# vONE-UNO.net
KiCad netlist of a schematic drawn in EAGLE
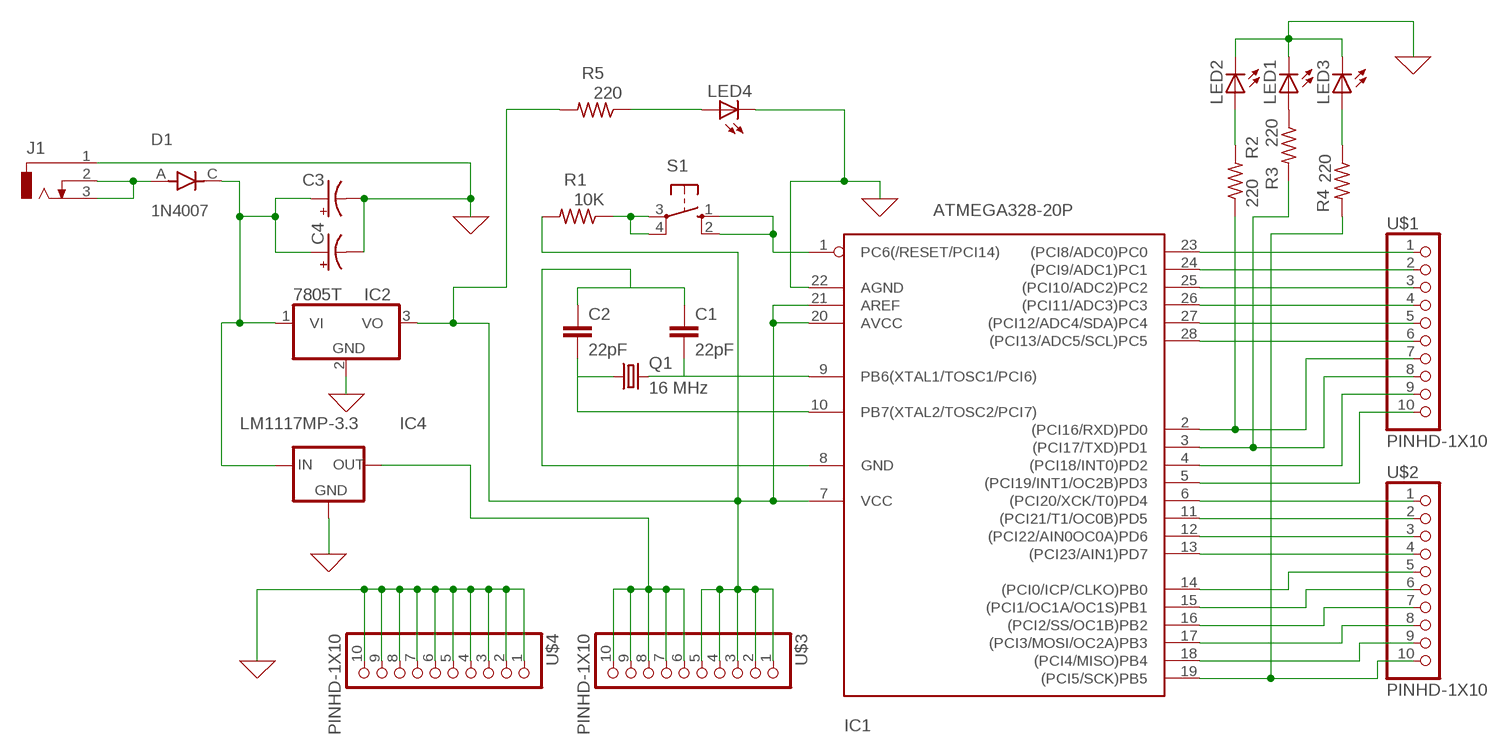
[diagram p0: schematic, sheet 1]

(export (version "E")
  (design (tool "Eeschema 10.0.6"))
  (components
    (comp (ref "C1")
      (value "22pF")
      (footprint "eagle-import:C2.5-3")
      (libsource (lib "eagle-import") (part "C2,5-3"))
    )
    (comp (ref "C2")
      (value "22pF")
      (footprint "eagle-import:C2.5-3")
      (libsource (lib "eagle-import") (part "C2,5-3"))
    )
    (comp (ref "C3")
      (value "CPOL-USE2,5-6E")
      (footprint "eagle-import:E2,5-6E")
      (libsource (lib "eagle-import") (part "CPOL-USE2,5-6E"))
    )
    (comp (ref "C4")
      (value "CPOL-USE2,5-6E")
      (footprint "eagle-import:E2,5-6E")
      (libsource (lib "eagle-import") (part "CPOL-USE2,5-6E"))
    )
    (comp (ref "D1")
      (value "1N4007")
      (footprint "eagle-import:DIOAD1060W80L520D270")
      (fields (field (name "MF") "ON Semiconductor"))
      (libsource (lib "eagle-import") (part "1N4007"))
    )
    (comp (ref "IC1")
      (value "ATMEGA328-20P")
      (footprint "eagle-import:DIL28-3")
      (libsource (lib "eagle-import") (part "ATMEGA328P-20"))
    )
    (comp (ref "IC2")
      (value "7805T")
      (footprint "eagle-import:TO220H")
      (libsource (lib "eagle-import") (part "78T05"))
    )
    (comp (ref "IC4")
      (value "LM1117MP-3.3")
      (footprint "eagle-import:SOT223")
      (fields (field (name "MF") "Texas Instruments"))
      (libsource (lib "eagle-import") (part "LM1117?-MP3.3"))
    )
    (comp (ref "J1")
      (value "DCJ0303")
      (footprint "eagle-import:DCJ0303")
      (libsource (lib "eagle-import") (part "DCJ0303"))
    )
    (comp (ref "LED1")
      (value "LED5MM")
      (footprint "eagle-import:LED5MM")
      (libsource (lib "eagle-import") (part "LED5MM"))
    )
    (comp (ref "LED2")
      (value "LED5MM")
      (footprint "eagle-import:LED5MM")
      (libsource (lib "eagle-import") (part "LED5MM"))
    )
    (comp (ref "LED3")
      (value "LED5MM")
      (footprint "eagle-import:LED5MM")
      (libsource (lib "eagle-import") (part "LED5MM"))
    )
    (comp (ref "LED4")
      (value "LED5MM")
      (footprint "eagle-import:LED5MM")
      (libsource (lib "eagle-import") (part "LED5MM"))
    )
    (comp (ref "Q1")
      (value "16 MHz")
      (footprint "eagle-import:HC49_S")
      (libsource (lib "eagle-import") (part "CRYSTALHC49S"))
    )
    (comp (ref "R1")
      (value "10K")
      (footprint "eagle-import:0805-THM")
      (libsource (lib "eagle-import") (part "FLIPFLOP-RES"))
    )
    (comp (ref "R2")
      (value "220")
      (footprint "eagle-import:0805-THM")
      (libsource (lib "eagle-import") (part "FLIPFLOP-RES"))
    )
    (comp (ref "R3")
      (value "220")
      (footprint "eagle-import:0805-THM")
      (libsource (lib "eagle-import") (part "FLIPFLOP-RES"))
    )
    (comp (ref "R4")
      (value "220")
      (footprint "eagle-import:0805-THM")
      (libsource (lib "eagle-import") (part "FLIPFLOP-RES"))
    )
    (comp (ref "R5")
      (value "220")
      (footprint "eagle-import:0805-THM")
      (libsource (lib "eagle-import") (part "FLIPFLOP-RES"))
    )
    (comp (ref "S1")
      (value "10-XX")
      (footprint "eagle-import:B3F-10XX")
      (fields (field (name "MPN") "B3F-1000"))
      (libsource (lib "eagle-import") (part "10-XX"))
    )
    (comp (ref "U$1")
      (value "PINHD-1X10")
      (footprint "eagle-import:1X10-BIG")
      (libsource (lib "eagle-import") (part "PINHD-1X10"))
    )
    (comp (ref "U$2")
      (value "PINHD-1X10")
      (footprint "eagle-import:1X10-BIG")
      (libsource (lib "eagle-import") (part "PINHD-1X10"))
    )
    (comp (ref "U$3")
      (value "PINHD-1X10")
      (footprint "eagle-import:1X10-BIG")
      (libsource (lib "eagle-import") (part "PINHD-1X10"))
    )
    (comp (ref "U$4")
      (value "PINHD-1X10")
      (footprint "eagle-import:1X10-BIG")
      (libsource (lib "eagle-import") (part "PINHD-1X10"))
    )
  )
  (nets
    (net (code "1") (name "GND") (class "Default")
      (node (ref "C3") (pin "-") (pinfunction "-_-") (pintype "passive"))
      (node (ref "C4") (pin "-") (pinfunction "-_-") (pintype "passive"))
      (node (ref "IC1") (pin "22") (pinfunction "AGND_22") (pintype "bidirectional"))
      (node (ref "IC2") (pin "2") (pinfunction "GND_2") (pintype "passive"))
      (node (ref "IC4") (pin "1") (pinfunction "GND_1") (pintype "input"))
      (node (ref "J1") (pin "1") (pinfunction "1_1") (pintype "passive"))
      (node (ref "LED1") (pin "K") (pinfunction "C_K") (pintype "passive"))
      (node (ref "LED2") (pin "K") (pinfunction "C_K") (pintype "passive"))
      (node (ref "LED3") (pin "K") (pinfunction "C_K") (pintype "passive"))
      (node (ref "LED4") (pin "K") (pinfunction "C_K") (pintype "passive"))
      (node (ref "U$4") (pin "1") (pinfunction "1_1") (pintype "passive"))
      (node (ref "U$4") (pin "10") (pinfunction "10_10") (pintype "passive"))
      (node (ref "U$4") (pin "2") (pinfunction "2_2") (pintype "passive"))
      (node (ref "U$4") (pin "3") (pinfunction "3_3") (pintype "passive"))
      (node (ref "U$4") (pin "4") (pinfunction "4_4") (pintype "passive"))
      (node (ref "U$4") (pin "5") (pinfunction "5_5") (pintype "passive"))
      (node (ref "U$4") (pin "6") (pinfunction "6_6") (pintype "passive"))
      (node (ref "U$4") (pin "7") (pinfunction "7_7") (pintype "passive"))
      (node (ref "U$4") (pin "8") (pinfunction "8_8") (pintype "passive"))
      (node (ref "U$4") (pin "9") (pinfunction "9_9") (pintype "passive"))
    )
    (net (code "2") (name "Net-(D1-PadA)") (class "Default")
      (node (ref "D1") (pin "A") (pinfunction "A_A") (pintype "passive"))
      (node (ref "J1") (pin "2") (pinfunction "2_2") (pintype "passive"))
      (node (ref "J1") (pin "3") (pinfunction "3_3") (pintype "passive"))
    )
    (net (code "3") (name "Net-(IC1-(PCI0{slash}ICP{slash}CLKO)PB0)") (class "Default")
      (node (ref "IC1") (pin "14") (pinfunction "(PCI0/ICP/CLKO)PB0_14") (pintype "bidirectional"))
      (node (ref "U$2") (pin "5") (pinfunction "5_5") (pintype "passive"))
    )
    (net (code "4") (name "Net-(IC1-(PCI1{slash}OC1A{slash}OC1S)PB1)") (class "Default")
      (node (ref "IC1") (pin "15") (pinfunction "(PCI1/OC1A/OC1S)PB1_15") (pintype "bidirectional"))
      (node (ref "U$2") (pin "6") (pinfunction "6_6") (pintype "passive"))
    )
    (net (code "5") (name "Net-(IC1-(PCI2{slash}SS{slash}OC1B)PB2)") (class "Default")
      (node (ref "IC1") (pin "16") (pinfunction "(PCI2/SS/OC1B)PB2_16") (pintype "bidirectional"))
      (node (ref "U$2") (pin "7") (pinfunction "7_7") (pintype "passive"))
    )
    (net (code "6") (name "Net-(IC1-(PCI3{slash}MOSI{slash}OC2A)PB3)") (class "Default")
      (node (ref "IC1") (pin "17") (pinfunction "(PCI3/MOSI/OC2A)PB3_17") (pintype "bidirectional"))
      (node (ref "U$2") (pin "8") (pinfunction "8_8") (pintype "passive"))
    )
    (net (code "7") (name "Net-(IC1-(PCI4{slash}MISO)PB4)") (class "Default")
      (node (ref "IC1") (pin "18") (pinfunction "(PCI4/MISO)PB4_18") (pintype "bidirectional"))
      (node (ref "U$2") (pin "9") (pinfunction "9_9") (pintype "passive"))
    )
    (net (code "8") (name "Net-(IC1-(PCI5{slash}SCK)PB5)") (class "Default")
      (node (ref "IC1") (pin "19") (pinfunction "(PCI5/SCK)PB5_19") (pintype "bidirectional"))
      (node (ref "R4") (pin "2") (pinfunction "2_2") (pintype "passive"))
      (node (ref "U$2") (pin "10") (pinfunction "10_10") (pintype "passive"))
    )
    (net (code "9") (name "Net-(IC1-(PCI8{slash}ADC0)PC0)") (class "Default")
      (node (ref "IC1") (pin "23") (pinfunction "(PCI8/ADC0)PC0_23") (pintype "bidirectional"))
      (node (ref "U$1") (pin "1") (pinfunction "1_1") (pintype "passive"))
    )
    (net (code "10") (name "Net-(IC1-(PCI9{slash}ADC1)PC1)") (class "Default")
      (node (ref "IC1") (pin "24") (pinfunction "(PCI9/ADC1)PC1_24") (pintype "bidirectional"))
      (node (ref "U$1") (pin "2") (pinfunction "2_2") (pintype "passive"))
    )
    (net (code "11") (name "Net-(IC1-(PCI10{slash}ADC2)PC2)") (class "Default")
      (node (ref "IC1") (pin "25") (pinfunction "(PCI10/ADC2)PC2_25") (pintype "bidirectional"))
      (node (ref "U$1") (pin "3") (pinfunction "3_3") (pintype "passive"))
    )
    (net (code "12") (name "Net-(IC1-(PCI11{slash}ADC3)PC3)") (class "Default")
      (node (ref "IC1") (pin "26") (pinfunction "(PCI11/ADC3)PC3_26") (pintype "bidirectional"))
      (node (ref "U$1") (pin "4") (pinfunction "4_4") (pintype "passive"))
    )
    (net (code "13") (name "Net-(IC1-(PCI12{slash}ADC4{slash}SDA)PC4)") (class "Default")
      (node (ref "IC1") (pin "27") (pinfunction "(PCI12/ADC4/SDA)PC4_27") (pintype "bidirectional"))
      (node (ref "U$1") (pin "5") (pinfunction "5_5") (pintype "passive"))
    )
    (net (code "14") (name "Net-(IC1-(PCI13{slash}ADC5{slash}SCL)PC5)") (class "Default")
      (node (ref "IC1") (pin "28") (pinfunction "(PCI13/ADC5/SCL)PC5_28") (pintype "bidirectional"))
      (node (ref "U$1") (pin "6") (pinfunction "6_6") (pintype "passive"))
    )
    (net (code "15") (name "Net-(IC1-(PCI16{slash}RXD)PD0)") (class "Default")
      (node (ref "IC1") (pin "2") (pinfunction "(PCI16/RXD)PD0_2") (pintype "bidirectional"))
      (node (ref "R3") (pin "1") (pinfunction "1_1") (pintype "passive"))
      (node (ref "U$1") (pin "7") (pinfunction "7_7") (pintype "passive"))
    )
    (net (code "16") (name "Net-(IC1-(PCI17{slash}TXD)PD1)") (class "Default")
      (node (ref "IC1") (pin "3") (pinfunction "(PCI17/TXD)PD1_3") (pintype "bidirectional"))
      (node (ref "R2") (pin "2") (pinfunction "2_2") (pintype "passive"))
      (node (ref "U$1") (pin "8") (pinfunction "8_8") (pintype "passive"))
    )
    (net (code "17") (name "Net-(IC1-(PCI18{slash}INT0)PD2)") (class "Default")
      (node (ref "IC1") (pin "4") (pinfunction "(PCI18/INT0)PD2_4") (pintype "bidirectional"))
      (node (ref "U$1") (pin "9") (pinfunction "9_9") (pintype "passive"))
    )
    (net (code "18") (name "Net-(IC1-(PCI19{slash}INT1{slash}OC2B)PD3)") (class "Default")
      (node (ref "IC1") (pin "5") (pinfunction "(PCI19/INT1/OC2B)PD3_5") (pintype "bidirectional"))
      (node (ref "U$1") (pin "10") (pinfunction "10_10") (pintype "passive"))
    )
    (net (code "19") (name "Net-(IC1-(PCI20{slash}XCK{slash}T0)PD4)") (class "Default")
      (node (ref "IC1") (pin "6") (pinfunction "(PCI20/XCK/T0)PD4_6") (pintype "bidirectional"))
      (node (ref "U$2") (pin "1") (pinfunction "1_1") (pintype "passive"))
    )
    (net (code "20") (name "Net-(IC1-(PCI21{slash}T1{slash}OC0B)PD5)") (class "Default")
      (node (ref "IC1") (pin "11") (pinfunction "(PCI21/T1/OC0B)PD5_11") (pintype "bidirectional"))
      (node (ref "U$2") (pin "2") (pinfunction "2_2") (pintype "passive"))
    )
    (net (code "21") (name "Net-(IC1-(PCI22{slash}AIN0OC0A)PD6)") (class "Default")
      (node (ref "IC1") (pin "12") (pinfunction "(PCI22/AIN0OC0A)PD6_12") (pintype "bidirectional"))
      (node (ref "U$2") (pin "3") (pinfunction "3_3") (pintype "passive"))
    )
    (net (code "22") (name "Net-(IC1-(PCI23{slash}AIN1)PD7)") (class "Default")
      (node (ref "IC1") (pin "13") (pinfunction "(PCI23/AIN1)PD7_13") (pintype "bidirectional"))
      (node (ref "U$2") (pin "4") (pinfunction "4_4") (pintype "passive"))
    )
    (net (code "23") (name "Net-(IC1-AREF)") (class "Default")
      (node (ref "IC1") (pin "20") (pinfunction "AVCC_20") (pintype "bidirectional"))
      (node (ref "IC1") (pin "21") (pinfunction "AREF_21") (pintype "bidirectional"))
      (node (ref "IC1") (pin "7") (pinfunction "VCC_7") (pintype "bidirectional"))
      (node (ref "IC2") (pin "3") (pinfunction "VO_3") (pintype "passive"))
      (node (ref "R1") (pin "2") (pinfunction "2_2") (pintype "passive"))
      (node (ref "R5") (pin "2") (pinfunction "2_2") (pintype "passive"))
      (node (ref "U$3") (pin "1") (pinfunction "1_1") (pintype "passive"))
      (node (ref "U$3") (pin "2") (pinfunction "2_2") (pintype "passive"))
      (node (ref "U$3") (pin "3") (pinfunction "3_3") (pintype "passive"))
      (node (ref "U$3") (pin "4") (pinfunction "4_4") (pintype "passive"))
      (node (ref "U$3") (pin "5") (pinfunction "5_5") (pintype "passive"))
    )
    (net (code "24") (name "Net-(IC1-GND)") (class "Default")
      (node (ref "C1") (pin "1") (pinfunction "1_1") (pintype "passive"))
      (node (ref "C2") (pin "1") (pinfunction "1_1") (pintype "passive"))
      (node (ref "IC1") (pin "8") (pinfunction "GND_8") (pintype "bidirectional"))
    )
    (net (code "25") (name "Net-(IC1-PB6(XTAL1{slash}TOSC1{slash}PCI6))") (class "Default")
      (node (ref "C1") (pin "2") (pinfunction "2_2") (pintype "passive"))
      (node (ref "IC1") (pin "9") (pinfunction "PB6(XTAL1/TOSC1/PCI6)_9") (pintype "bidirectional"))
      (node (ref "Q1") (pin "2") (pinfunction "2_2") (pintype "passive"))
    )
    (net (code "26") (name "Net-(IC1-PB7(XTAL2{slash}TOSC2{slash}PCI7))") (class "Default")
      (node (ref "C2") (pin "2") (pinfunction "2_2") (pintype "passive"))
      (node (ref "IC1") (pin "10") (pinfunction "PB7(XTAL2/TOSC2/PCI7)_10") (pintype "bidirectional"))
      (node (ref "Q1") (pin "1") (pinfunction "1_1") (pintype "passive"))
    )
    (net (code "27") (name "Net-(IC1-PC6({slash}RESET{slash}PCI14))") (class "Default")
      (node (ref "IC1") (pin "1") (pinfunction "PC6(/RESET/PCI14)_1") (pintype "bidirectional"))
      (node (ref "S1") (pin "1") (pinfunction "S_1") (pintype "passive"))
      (node (ref "S1") (pin "2") (pinfunction "S1_2") (pintype "passive"))
    )
    (net (code "28") (name "Net-(IC2-VI)") (class "Default")
      (node (ref "C3") (pin "+") (pinfunction "+_+") (pintype "passive"))
      (node (ref "C4") (pin "+") (pinfunction "+_+") (pintype "passive"))
      (node (ref "D1") (pin "C") (pinfunction "C_C") (pintype "passive"))
      (node (ref "IC2") (pin "1") (pinfunction "VI_1") (pintype "input"))
      (node (ref "IC4") (pin "3") (pinfunction "IN_3") (pintype "input"))
    )
    (net (code "29") (name "Net-(IC4-OUT-Pad2)") (class "Default")
      (node (ref "IC4") (pin "2") (pinfunction "OUT_2") (pintype "passive"))
      (node (ref "IC4") (pin "4") (pinfunction "OUT_4") (pintype "passive"))
      (node (ref "U$3") (pin "10") (pinfunction "10_10") (pintype "passive"))
      (node (ref "U$3") (pin "6") (pinfunction "6_6") (pintype "passive"))
      (node (ref "U$3") (pin "7") (pinfunction "7_7") (pintype "passive"))
      (node (ref "U$3") (pin "8") (pinfunction "8_8") (pintype "passive"))
      (node (ref "U$3") (pin "9") (pinfunction "9_9") (pintype "passive"))
    )
    (net (code "30") (name "Net-(LED1-PadA)") (class "Default")
      (node (ref "LED1") (pin "A") (pinfunction "A_A") (pintype "passive"))
      (node (ref "R2") (pin "1") (pinfunction "1_1") (pintype "passive"))
    )
    (net (code "31") (name "Net-(LED2-PadA)") (class "Default")
      (node (ref "LED2") (pin "A") (pinfunction "A_A") (pintype "passive"))
      (node (ref "R3") (pin "2") (pinfunction "2_2") (pintype "passive"))
    )
    (net (code "32") (name "Net-(LED3-PadA)") (class "Default")
      (node (ref "LED3") (pin "A") (pinfunction "A_A") (pintype "passive"))
      (node (ref "R4") (pin "1") (pinfunction "1_1") (pintype "passive"))
    )
    (net (code "33") (name "Net-(LED4-PadA)") (class "Default")
      (node (ref "LED4") (pin "A") (pinfunction "A_A") (pintype "passive"))
      (node (ref "R5") (pin "1") (pinfunction "1_1") (pintype "passive"))
    )
    (net (code "34") (name "Net-(S1-P)") (class "Default")
      (node (ref "R1") (pin "1") (pinfunction "1_1") (pintype "passive"))
      (node (ref "S1") (pin "3") (pinfunction "P_3") (pintype "passive"))
      (node (ref "S1") (pin "4") (pinfunction "P1_4") (pintype "passive"))
    )
  )
)
